# SENSORS.net
KiCad netlist of a schematic drawn in Altium Designer
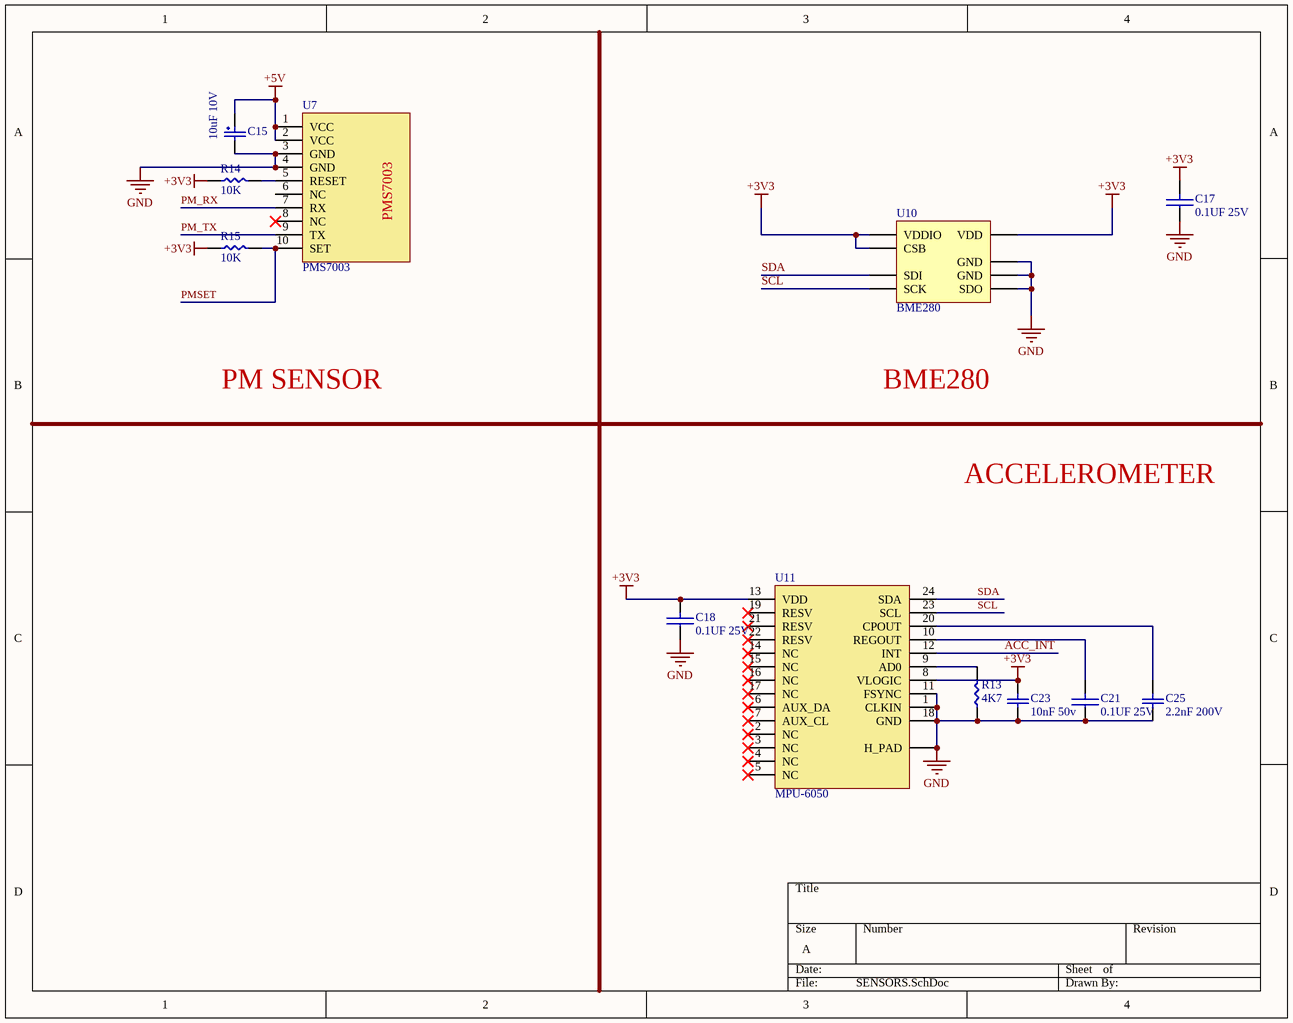
[diagram p0: SENSORS.SchDoc]

(export (version "E")
  (design (tool "Eeschema 10.0.6"))
  (components
    (comp (ref "C15")
      (value "10uF 10V")
      (footprint "C3216")
      (description "CAP TANT 10UF 10V 10% 1206")
      (fields
        (field (name "MANUFACTURER") "KEMET")
        (field (name "MANUFACTURER PART NUMBER") "T491A106K010AT")
      )
      (libsource (lib "salcox") (part "T491A106K010AT"))
    )
    (comp (ref "C17")
      (value "0.1UF 25V")
      (footprint "C0603")
      (description "CAP CER 0.1UF 25V X5R 0603")
      (fields
        (field (name "MANUFACTURER") "Kyocera AVX")
        (field (name "MANUFACTURER PART NUMBER") "06033D104KAT2A")
      )
      (libsource (lib "salcox") (part "06033D104KAT2A"))
    )
    (comp (ref "C18")
      (value "0.1UF 25V")
      (footprint "C0603")
      (description "CAP CER 0.1UF 25V X5R 0603")
      (fields
        (field (name "MANUFACTURER") "Kyocera AVX")
        (field (name "MANUFACTURER PART NUMBER") "06033D104KAT2A")
      )
      (libsource (lib "salcox") (part "06033D104KAT2A"))
    )
    (comp (ref "C21")
      (value "0.1UF 25V")
      (footprint "C0603")
      (description "CAP CER 0.1UF 25V X5R 0603")
      (fields
        (field (name "MANUFACTURER") "Kyocera AVX")
        (field (name "MANUFACTURER PART NUMBER") "06033D104KAT2A")
      )
      (libsource (lib "salcox") (part "06033D104KAT2A"))
    )
    (comp (ref "C23")
      (value "10nF 50v")
      (footprint "C0603")
      (description "Cap Ceramic 0.01uF 50V X7R 10% SMD 0603 125C Automotive T/R")
      (fields
        (field (name "MANUFACTURER") "Yageo")
        (field (name "MANUFACTURER PART NUMBER") "CC0603KRX7R9BB103")
      )
      (libsource (lib "salcoxschlib") (part "CC0603KRX7R9BB103 (2)"))
    )
    (comp (ref "C25")
      (value "2.2nF 200V")
      (footprint "C0603")
      (description "CAP CER 2200PF 200V X7R 0603")
      (fields
        (field (name "MANUFACTURER") "KEMET")
        (field (name "MANUFACTURER PART NUMBER") "C0603C222K2RACTU")
      )
      (libsource (lib "salcoxschlib") (part "C0603C222K2RACTU"))
    )
    (comp (ref "R13")
      (value "4K7")
      (footprint "R0603")
      (description "RES SMD 4.7K OHM 1% 1/10W 0603")
      (fields
        (field (name "MANUFACTURER") "Vishay")
        (field (name "MANUFACTURER PART NUMBER") "CRCW06034K70FKEA")
      )
      (libsource (lib "salcoxschlib") (part "CRCW06034K70FKEA"))
    )
    (comp (ref "R14")
      (value "10K")
      (footprint "R0603")
      (description "RES SMD 10K OHM 1% 1/10W 0603")
      (fields
        (field (name "MANUFACTURER") "Yageo")
        (field (name "MANUFACTURER PART NUMBER") "RC0603FR-0710KL")
      )
      (libsource (lib "salcox") (part "RC0603FR-0710KL"))
    )
    (comp (ref "R15")
      (value "10K")
      (footprint "R0603")
      (description "RES SMD 10K OHM 1% 1/10W 0603")
      (fields
        (field (name "MANUFACTURER") "Yageo")
        (field (name "MANUFACTURER PART NUMBER") "RC0603FR-0710KL")
      )
      (libsource (lib "salcox") (part "RC0603FR-0710KL"))
    )
    (comp (ref "U7") (value "PMS7003") (footprint "PMS7003") (libsource (lib "salcox") (part "PMS7003")))
    (comp (ref "U10")
      (value "BME280")
      (footprint "BME280")
      (description "Pressure, Temperature and Humidity Sensor Digital Output 1.8V 8-Pin LGA T/R")
      (fields (field (name "MANUFACTURER") "Bosch"))
      (libsource (lib "salcoxschlib") (part "BME280"))
    )
    (comp (ref "U11")
      (value "MPU-6050")
      (footprint "MPU6050")
      (description "IMU ACCEL/GYRO 3-AXIS I2C 24QFN")
      (fields (field (name "MANUFACTURER") "TDK InvenSense"))
      (libsource (lib "salcoxschlib") (part "MPU-6050"))
    )
  )
  (nets
    (net (code "1") (name "+3V3") (class "Default")
      (node (ref "C17") (pin "2") (pinfunction "2_2") (pintype "passive"))
      (node (ref "C18") (pin "2") (pinfunction "2_2") (pintype "passive"))
      (node (ref "C23") (pin "2") (pinfunction "2_2") (pintype "passive"))
      (node (ref "R14") (pin "1") (pinfunction "1_1") (pintype "passive"))
      (node (ref "R15") (pin "1") (pinfunction "1_1") (pintype "passive"))
      (node (ref "U10") (pin "2") (pinfunction "CSB_2") (pintype "passive"))
      (node (ref "U10") (pin "6") (pinfunction "VDDIO_6") (pintype "passive"))
      (node (ref "U10") (pin "8") (pinfunction "VDD_8") (pintype "passive"))
      (node (ref "U11") (pin "13") (pinfunction "VDD_13") (pintype "passive"))
      (node (ref "U11") (pin "8") (pinfunction "VLOGIC_8") (pintype "passive"))
    )
    (net (code "2") (name "+5V") (class "Default")
      (node (ref "C15") (pin "2") (pinfunction "2_2") (pintype "passive"))
      (node (ref "U7") (pin "1") (pinfunction "VCC_1") (pintype "passive"))
      (node (ref "U7") (pin "2") (pinfunction "VCC_2") (pintype "passive"))
    )
    (net (code "3") (name "/ACC_INT") (class "Default")
      (node (ref "U11") (pin "12") (pinfunction "INT_12") (pintype "passive"))
    )
    (net (code "4") (name "/PMSET") (class "Default")
      (node (ref "R15") (pin "2") (pinfunction "2_2") (pintype "passive"))
      (node (ref "U7") (pin "10") (pinfunction "SET_10") (pintype "passive"))
    )
    (net (code "5") (name "/PM_RX") (class "Default")
      (node (ref "U7") (pin "7") (pinfunction "RX_7") (pintype "passive"))
    )
    (net (code "6") (name "/PM_TX") (class "Default")
      (node (ref "U7") (pin "9") (pinfunction "TX_9") (pintype "passive"))
    )
    (net (code "7") (name "/SCL") (class "Default")
      (node (ref "U10") (pin "4") (pinfunction "SCK_4") (pintype "passive"))
      (node (ref "U11") (pin "23") (pinfunction "SCL_23") (pintype "passive"))
    )
    (net (code "8") (name "/SDA") (class "Default")
      (node (ref "U10") (pin "3") (pinfunction "SDI_3") (pintype "passive"))
      (node (ref "U11") (pin "24") (pinfunction "SDA_24") (pintype "passive"))
    )
    (net (code "9") (name "GND") (class "Default")
      (node (ref "C15") (pin "1") (pinfunction "1_1") (pintype "passive"))
      (node (ref "C17") (pin "1") (pinfunction "1_1") (pintype "passive"))
      (node (ref "C18") (pin "1") (pinfunction "1_1") (pintype "passive"))
      (node (ref "C21") (pin "1") (pinfunction "1_1") (pintype "passive"))
      (node (ref "C23") (pin "1") (pinfunction "1_1") (pintype "passive"))
      (node (ref "C25") (pin "1") (pinfunction "1_1") (pintype "passive"))
      (node (ref "R13") (pin "1") (pinfunction "1_1") (pintype "passive"))
      (node (ref "U10") (pin "1") (pinfunction "GND_1") (pintype "passive"))
      (node (ref "U10") (pin "5") (pinfunction "SDO_5") (pintype "passive"))
      (node (ref "U10") (pin "7") (pinfunction "GND_7") (pintype "passive"))
      (node (ref "U11") (pin "1") (pinfunction "CLKIN_1") (pintype "passive"))
      (node (ref "U11") (pin "11") (pinfunction "FSYNC_11") (pintype "passive"))
      (node (ref "U11") (pin "18") (pinfunction "GND_18") (pintype "passive"))
      (node (ref "U11") (pin "25") (pinfunction "H_PAD_25") (pintype "passive"))
      (node (ref "U7") (pin "3") (pinfunction "GND_3") (pintype "passive"))
      (node (ref "U7") (pin "4") (pinfunction "GND_4") (pintype "passive"))
    )
    (net (code "10") (name "Net-(U7-RESET)") (class "Default")
      (node (ref "R14") (pin "2") (pinfunction "2_2") (pintype "passive"))
      (node (ref "U7") (pin "5") (pinfunction "RESET_5") (pintype "passive"))
    )
    (net (code "11") (name "Net-(U11-AD0)") (class "Default")
      (node (ref "R13") (pin "2") (pinfunction "2_2") (pintype "passive"))
      (node (ref "U11") (pin "9") (pinfunction "AD0_9") (pintype "passive"))
    )
    (net (code "12") (name "Net-(U11-CPOUT)") (class "Default")
      (node (ref "C25") (pin "2") (pinfunction "2_2") (pintype "passive"))
      (node (ref "U11") (pin "20") (pinfunction "CPOUT_20") (pintype "passive"))
    )
    (net (code "13") (name "Net-(U11-REGOUT)") (class "Default")
      (node (ref "C21") (pin "2") (pinfunction "2_2") (pintype "passive"))
      (node (ref "U11") (pin "10") (pinfunction "REGOUT_10") (pintype "passive"))
    )
    (net (code "14") (name "unconnected-(U7-NC-Pad6)") (class "Default")
      (node (ref "U7") (pin "6") (pinfunction "NC_6") (pintype "passive"))
    )
    (net (code "15") (name "unconnected-(U7-NC-Pad8)") (class "Default")
      (node (ref "U7") (pin "8") (pinfunction "NC_8") (pintype "passive+no_connect"))
    )
    (net (code "16") (name "unconnected-(U11-AUX_CL-Pad7)") (class "Default")
      (node (ref "U11") (pin "7") (pinfunction "AUX_CL_7") (pintype "passive+no_connect"))
    )
    (net (code "17") (name "unconnected-(U11-AUX_DA-Pad6)") (class "Default")
      (node (ref "U11") (pin "6") (pinfunction "AUX_DA_6") (pintype "passive+no_connect"))
    )
    (net (code "18") (name "unconnected-(U11-NC-Pad2)") (class "Default")
      (node (ref "U11") (pin "2") (pinfunction "NC_2") (pintype "passive+no_connect"))
    )
    (net (code "19") (name "unconnected-(U11-NC-Pad3)") (class "Default")
      (node (ref "U11") (pin "3") (pinfunction "NC_3") (pintype "passive+no_connect"))
    )
    (net (code "20") (name "unconnected-(U11-NC-Pad4)") (class "Default")
      (node (ref "U11") (pin "4") (pinfunction "NC_4") (pintype "passive+no_connect"))
    )
    (net (code "21") (name "unconnected-(U11-NC-Pad5)") (class "Default")
      (node (ref "U11") (pin "5") (pinfunction "NC_5") (pintype "passive+no_connect"))
    )
    (net (code "22") (name "unconnected-(U11-NC-Pad14)") (class "Default")
      (node (ref "U11") (pin "14") (pinfunction "NC_14") (pintype "passive+no_connect"))
    )
    (net (code "23") (name "unconnected-(U11-NC-Pad15)") (class "Default")
      (node (ref "U11") (pin "15") (pinfunction "NC_15") (pintype "passive+no_connect"))
    )
    (net (code "24") (name "unconnected-(U11-NC-Pad16)") (class "Default")
      (node (ref "U11") (pin "16") (pinfunction "NC_16") (pintype "passive+no_connect"))
    )
    (net (code "25") (name "unconnected-(U11-NC-Pad17)") (class "Default")
      (node (ref "U11") (pin "17") (pinfunction "NC_17") (pintype "passive+no_connect"))
    )
    (net (code "26") (name "unconnected-(U11-RESV-Pad19)") (class "Default")
      (node (ref "U11") (pin "19") (pinfunction "RESV_19") (pintype "passive+no_connect"))
    )
    (net (code "27") (name "unconnected-(U11-RESV-Pad21)") (class "Default")
      (node (ref "U11") (pin "21") (pinfunction "RESV_21") (pintype "passive+no_connect"))
    )
    (net (code "28") (name "unconnected-(U11-RESV-Pad22)") (class "Default")
      (node (ref "U11") (pin "22") (pinfunction "RESV_22") (pintype "passive+no_connect"))
    )
  )
)
